# esp8266player3.net
KiCad netlist of a schematic drawn in EAGLE
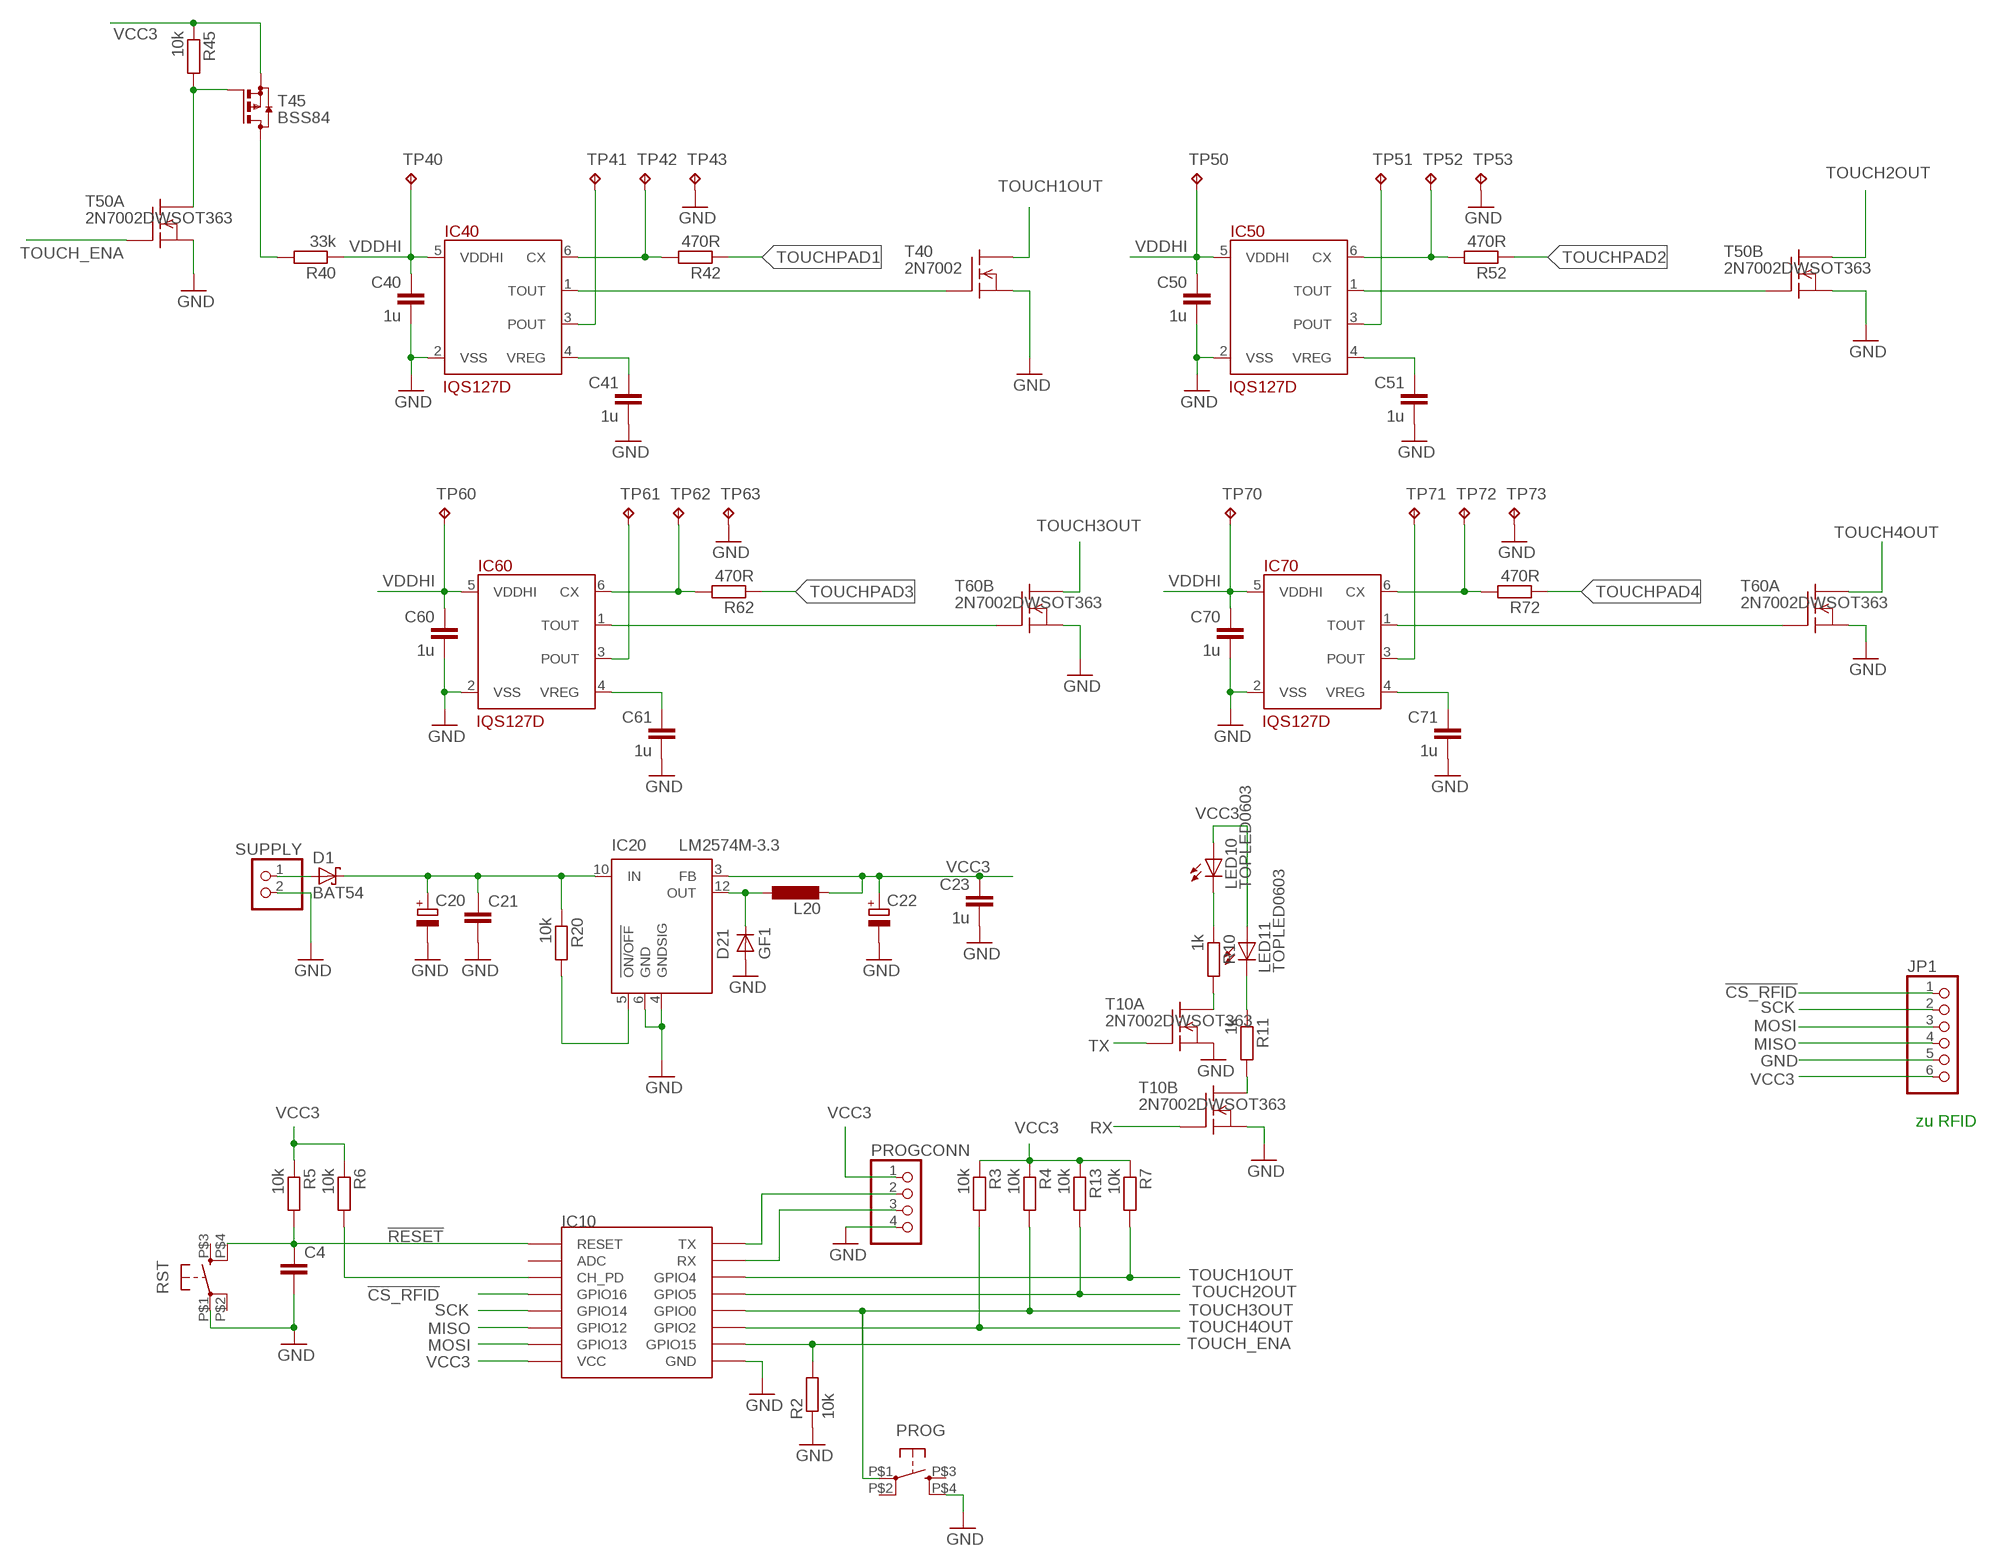
[diagram p0: schematic, sheet 1]

(export (version "E")
  (design (tool "Eeschema 10.0.6"))
  (components
    (comp (ref "C4")
      (value "C-EUC0603")
      (footprint "eagle-import:C0603")
      (libsource (lib "eagle-import") (part "C-EUC0603"))
    )
    (comp (ref "C20")
      (value "CPOL-EUC")
      (footprint "eagle-import:PANASONIC_C")
      (libsource (lib "eagle-import") (part "CPOL-EUC"))
    )
    (comp (ref "C21")
      (value "C-EUC1206")
      (footprint "eagle-import:C1206")
      (libsource (lib "eagle-import") (part "C-EUC1206"))
    )
    (comp (ref "C22")
      (value "CPOL-EUF")
      (footprint "eagle-import:PANASONIC_F")
      (libsource (lib "eagle-import") (part "CPOL-EUF"))
    )
    (comp (ref "C23")
      (value "1u")
      (footprint "eagle-import:C0603")
      (libsource (lib "eagle-import") (part "C-EUC0603"))
    )
    (comp (ref "C40")
      (value "1u")
      (footprint "eagle-import:C0603")
      (libsource (lib "eagle-import") (part "C-EUC0603"))
    )
    (comp (ref "C41")
      (value "1u")
      (footprint "eagle-import:C0603")
      (libsource (lib "eagle-import") (part "C-EUC0603"))
    )
    (comp (ref "C50")
      (value "1u")
      (footprint "eagle-import:C0603")
      (libsource (lib "eagle-import") (part "C-EUC0603"))
    )
    (comp (ref "C51")
      (value "1u")
      (footprint "eagle-import:C0603")
      (libsource (lib "eagle-import") (part "C-EUC0603"))
    )
    (comp (ref "C60")
      (value "1u")
      (footprint "eagle-import:C0603")
      (libsource (lib "eagle-import") (part "C-EUC0603"))
    )
    (comp (ref "C61")
      (value "1u")
      (footprint "eagle-import:C0603")
      (libsource (lib "eagle-import") (part "C-EUC0603"))
    )
    (comp (ref "C70")
      (value "1u")
      (footprint "eagle-import:C0603")
      (libsource (lib "eagle-import") (part "C-EUC0603"))
    )
    (comp (ref "C71")
      (value "1u")
      (footprint "eagle-import:C0603")
      (libsource (lib "eagle-import") (part "C-EUC0603"))
    )
    (comp (ref "D1")
      (value "BAT54")
      (footprint "eagle-import:SOT23")
      (libsource (lib "eagle-import") (part "BAT54"))
    )
    (comp (ref "D21")
      (value "GF1")
      (footprint "eagle-import:SMA-DO214AC")
      (libsource (lib "eagle-import") (part "GF1"))
    )
    (comp (ref "IC10")
      (value "ESP12SMD")
      (footprint "eagle-import:ESP12-SMD")
      (libsource (lib "eagle-import") (part "ESP12SMD"))
    )
    (comp (ref "IC20")
      (value "LM2574M-3.3")
      (footprint "eagle-import:SO14W")
      (libsource (lib "eagle-import") (part "LM2574?-M3.3"))
    )
    (comp (ref "IC40")
      (value "IQS127D")
      (footprint "eagle-import:SOT23-6")
      (libsource (lib "eagle-import") (part "IQS127D"))
    )
    (comp (ref "IC50")
      (value "IQS127D")
      (footprint "eagle-import:SOT23-6")
      (libsource (lib "eagle-import") (part "IQS127D"))
    )
    (comp (ref "IC60")
      (value "IQS127D")
      (footprint "eagle-import:SOT23-6")
      (libsource (lib "eagle-import") (part "IQS127D"))
    )
    (comp (ref "IC70")
      (value "IQS127D")
      (footprint "eagle-import:SOT23-6")
      (libsource (lib "eagle-import") (part "IQS127D"))
    )
    (comp (ref "JP1")
      (value "PINHD-1X6")
      (footprint "eagle-import:1X06")
      (libsource (lib "eagle-import") (part "PINHD-1X6"))
    )
    (comp (ref "L20")
      (value "L-EUSRR0603")
      (footprint "eagle-import:SRR6603-BOURNS")
      (libsource (lib "eagle-import") (part "L-EUSRR0603"))
    )
    (comp (ref "LED10")
      (value "TOPLED0603")
      (footprint "eagle-import:LED-0603-OSRAM")
      (libsource (lib "eagle-import") (part "TOPLED0603"))
    )
    (comp (ref "LED11")
      (value "TOPLED0603")
      (footprint "eagle-import:LED-0603-OSRAM")
      (libsource (lib "eagle-import") (part "TOPLED0603"))
    )
    (comp (ref "PROG")
      (value "10-XXTL3305")
      (footprint "eagle-import:TL3305")
      (libsource (lib "eagle-import") (part "10-XXTL3305"))
    )
    (comp (ref "PROGCONN")
      (value "PINHD-1X4")
      (footprint "eagle-import:1X04")
      (libsource (lib "eagle-import") (part "PINHD-1X4"))
    )
    (comp (ref "R2")
      (value "10k")
      (footprint "eagle-import:R0603@1")
      (libsource (lib "eagle-import") (part "R-EU_R0603"))
    )
    (comp (ref "R3")
      (value "10k")
      (footprint "eagle-import:R0603@1")
      (libsource (lib "eagle-import") (part "R-EU_R0603"))
    )
    (comp (ref "R4")
      (value "10k")
      (footprint "eagle-import:R0603@1")
      (libsource (lib "eagle-import") (part "R-EU_R0603"))
    )
    (comp (ref "R5")
      (value "10k")
      (footprint "eagle-import:R0603@1")
      (libsource (lib "eagle-import") (part "R-EU_R0603"))
    )
    (comp (ref "R6")
      (value "10k")
      (footprint "eagle-import:R0603@1")
      (libsource (lib "eagle-import") (part "R-EU_R0603"))
    )
    (comp (ref "R7")
      (value "10k")
      (footprint "eagle-import:R0603@1")
      (libsource (lib "eagle-import") (part "R-EU_R0603"))
    )
    (comp (ref "R10")
      (value "1k")
      (footprint "eagle-import:R0603@1")
      (libsource (lib "eagle-import") (part "R-EU_R0603"))
    )
    (comp (ref "R11")
      (value "1k")
      (footprint "eagle-import:R0603@1")
      (libsource (lib "eagle-import") (part "R-EU_R0603"))
    )
    (comp (ref "R13")
      (value "10k")
      (footprint "eagle-import:R0603@1")
      (libsource (lib "eagle-import") (part "R-EU_R0603"))
    )
    (comp (ref "R20")
      (value "10k")
      (footprint "eagle-import:R0603@1")
      (libsource (lib "eagle-import") (part "R-EU_R0603"))
    )
    (comp (ref "R40")
      (value "33k")
      (footprint "eagle-import:R0603@1")
      (libsource (lib "eagle-import") (part "R-EU_R0603"))
    )
    (comp (ref "R42")
      (value "470R")
      (footprint "eagle-import:R0603@1")
      (libsource (lib "eagle-import") (part "R-EU_R0603"))
    )
    (comp (ref "R45")
      (value "10k")
      (footprint "eagle-import:R0603@1")
      (libsource (lib "eagle-import") (part "R-EU_R0603"))
    )
    (comp (ref "R52")
      (value "470R")
      (footprint "eagle-import:R0603@1")
      (libsource (lib "eagle-import") (part "R-EU_R0603"))
    )
    (comp (ref "R62")
      (value "470R")
      (footprint "eagle-import:R0603@1")
      (libsource (lib "eagle-import") (part "R-EU_R0603"))
    )
    (comp (ref "R72")
      (value "470R")
      (footprint "eagle-import:R0603@1")
      (libsource (lib "eagle-import") (part "R-EU_R0603"))
    )
    (comp (ref "RST")
      (value "10-XXTL3305")
      (footprint "eagle-import:TL3305")
      (libsource (lib "eagle-import") (part "10-XXTL3305"))
    )
    (comp (ref "SUPPLY")
      (value "PINHD-1X2")
      (footprint "eagle-import:1X02")
      (libsource (lib "eagle-import") (part "PINHD-1X2"))
    )
    (comp (ref "T10")
      (value "2N7002DWSOT363")
      (footprint "eagle-import:SOT363")
      (libsource (lib "eagle-import") (part "2N7002DWSOT363"))
    )
    (comp (ref "T40")
      (value "2N7002")
      (footprint "eagle-import:SOT23")
      (libsource (lib "eagle-import") (part "2N7002"))
    )
    (comp (ref "T45")
      (value "BSS84")
      (footprint "eagle-import:SOT23")
      (libsource (lib "eagle-import") (part "BSS84"))
    )
    (comp (ref "T50")
      (value "2N7002DWSOT363")
      (footprint "eagle-import:SOT363")
      (libsource (lib "eagle-import") (part "2N7002DWSOT363"))
    )
    (comp (ref "T60")
      (value "2N7002DWSOT363")
      (footprint "eagle-import:SOT363")
      (libsource (lib "eagle-import") (part "2N7002DWSOT363"))
    )
    (comp (ref "TP40")
      (value "TPB1,27")
      (footprint "eagle-import:B1,27")
      (libsource (lib "eagle-import") (part "TPB1,27"))
    )
    (comp (ref "TP41")
      (value "TPB1,27")
      (footprint "eagle-import:B1,27")
      (libsource (lib "eagle-import") (part "TPB1,27"))
    )
    (comp (ref "TP42")
      (value "TPB1,27")
      (footprint "eagle-import:B1,27")
      (libsource (lib "eagle-import") (part "TPB1,27"))
    )
    (comp (ref "TP43")
      (value "TPB1,27")
      (footprint "eagle-import:B1,27")
      (libsource (lib "eagle-import") (part "TPB1,27"))
    )
    (comp (ref "TP50")
      (value "TPB1,27")
      (footprint "eagle-import:B1,27")
      (libsource (lib "eagle-import") (part "TPB1,27"))
    )
    (comp (ref "TP51")
      (value "TPB1,27")
      (footprint "eagle-import:B1,27")
      (libsource (lib "eagle-import") (part "TPB1,27"))
    )
    (comp (ref "TP52")
      (value "TPB1,27")
      (footprint "eagle-import:B1,27")
      (libsource (lib "eagle-import") (part "TPB1,27"))
    )
    (comp (ref "TP53")
      (value "TPB1,27")
      (footprint "eagle-import:B1,27")
      (libsource (lib "eagle-import") (part "TPB1,27"))
    )
    (comp (ref "TP60")
      (value "TPB1,27")
      (footprint "eagle-import:B1,27")
      (libsource (lib "eagle-import") (part "TPB1,27"))
    )
    (comp (ref "TP61")
      (value "TPB1,27")
      (footprint "eagle-import:B1,27")
      (libsource (lib "eagle-import") (part "TPB1,27"))
    )
    (comp (ref "TP62")
      (value "TPB1,27")
      (footprint "eagle-import:B1,27")
      (libsource (lib "eagle-import") (part "TPB1,27"))
    )
    (comp (ref "TP63")
      (value "TPB1,27")
      (footprint "eagle-import:B1,27")
      (libsource (lib "eagle-import") (part "TPB1,27"))
    )
    (comp (ref "TP70")
      (value "TPB1,27")
      (footprint "eagle-import:B1,27")
      (libsource (lib "eagle-import") (part "TPB1,27"))
    )
    (comp (ref "TP71")
      (value "TPB1,27")
      (footprint "eagle-import:B1,27")
      (libsource (lib "eagle-import") (part "TPB1,27"))
    )
    (comp (ref "TP72")
      (value "TPB1,27")
      (footprint "eagle-import:B1,27")
      (libsource (lib "eagle-import") (part "TPB1,27"))
    )
    (comp (ref "TP73")
      (value "TPB1,27")
      (footprint "eagle-import:B1,27")
      (libsource (lib "eagle-import") (part "TPB1,27"))
    )
  )
  (nets
    (net (code "1") (name "/MISO") (class "Default")
      (node (ref "IC10") (pin "GPIO12") (pinfunction "GPIO12_GPIO12") (pintype "bidirectional"))
      (node (ref "JP1") (pin "4") (pinfunction "4_4") (pintype "passive"))
    )
    (net (code "2") (name "/MOSI") (class "Default")
      (node (ref "IC10") (pin "GPIO13") (pinfunction "GPIO13_GPIO13") (pintype "bidirectional"))
      (node (ref "JP1") (pin "3") (pinfunction "3_3") (pintype "passive"))
    )
    (net (code "3") (name "/RX") (class "Default")
      (node (ref "IC10") (pin "RXD0") (pinfunction "RX_RXD0") (pintype "bidirectional"))
      (node (ref "PROGCONN") (pin "3") (pinfunction "3_3") (pintype "passive"))
      (node (ref "T10") (pin "2") (pinfunction "G_2") (pintype "passive"))
    )
    (net (code "4") (name "/SCK") (class "Default")
      (node (ref "IC10") (pin "GPIO14") (pinfunction "GPIO14_GPIO14") (pintype "bidirectional"))
      (node (ref "JP1") (pin "2") (pinfunction "2_2") (pintype "passive"))
    )
    (net (code "5") (name "/TOUCH1OUT") (class "Default")
      (node (ref "IC10") (pin "GPIO4") (pinfunction "GPIO4_GPIO4") (pintype "bidirectional"))
      (node (ref "R7") (pin "2") (pinfunction "2_2") (pintype "passive"))
      (node (ref "T40") (pin "3") (pinfunction "D_3") (pintype "passive"))
    )
    (net (code "6") (name "/TOUCH2OUT") (class "Default")
      (node (ref "IC10") (pin "GPIO5") (pinfunction "GPIO5_GPIO5") (pintype "bidirectional"))
      (node (ref "R13") (pin "2") (pinfunction "2_2") (pintype "passive"))
      (node (ref "T50") (pin "6") (pinfunction "D_6") (pintype "passive"))
    )
    (net (code "7") (name "/TOUCH3OUT") (class "Default")
      (node (ref "IC10") (pin "GPIO0") (pinfunction "GPIO0_GPIO0") (pintype "bidirectional"))
      (node (ref "PROG") (pin "P$1") (pinfunction "P_P$1") (pintype "passive"))
      (node (ref "R4") (pin "2") (pinfunction "2_2") (pintype "passive"))
      (node (ref "T60") (pin "6") (pinfunction "D_6") (pintype "passive"))
    )
    (net (code "8") (name "/TOUCH4OUT") (class "Default")
      (node (ref "IC10") (pin "GPIO2") (pinfunction "GPIO2_GPIO2") (pintype "bidirectional"))
      (node (ref "R3") (pin "2") (pinfunction "2_2") (pintype "passive"))
      (node (ref "T60") (pin "3") (pinfunction "D_3") (pintype "passive"))
    )
    (net (code "9") (name "/TOUCH_ENA") (class "Default")
      (node (ref "IC10") (pin "GPIO15") (pinfunction "GPIO15_GPIO15") (pintype "bidirectional"))
      (node (ref "R2") (pin "2") (pinfunction "2_2") (pintype "passive"))
      (node (ref "T50") (pin "5") (pinfunction "G_5") (pintype "passive"))
    )
    (net (code "10") (name "/TX") (class "Default")
      (node (ref "IC10") (pin "TXD0") (pinfunction "TX_TXD0") (pintype "bidirectional"))
      (node (ref "PROGCONN") (pin "2") (pinfunction "2_2") (pintype "passive"))
      (node (ref "T10") (pin "5") (pinfunction "G_5") (pintype "passive"))
    )
    (net (code "11") (name "/VCC3") (class "Default")
      (node (ref "C22") (pin "+") (pinfunction "+_+") (pintype "passive"))
      (node (ref "C23") (pin "1") (pinfunction "1_1") (pintype "passive"))
      (node (ref "IC10") (pin "VCC") (pinfunction "VCC_VCC") (pintype "bidirectional"))
      (node (ref "IC20") (pin "3") (pinfunction "FB_3") (pintype "input"))
      (node (ref "JP1") (pin "6") (pinfunction "6_6") (pintype "passive"))
      (node (ref "L20") (pin "2") (pinfunction "2_2") (pintype "passive"))
      (node (ref "LED10") (pin "A@1") (pinfunction "A_A@1") (pintype "passive"))
      (node (ref "LED11") (pin "A@1") (pinfunction "A_A@1") (pintype "passive"))
      (node (ref "PROGCONN") (pin "1") (pinfunction "1_1") (pintype "passive"))
      (node (ref "R13") (pin "1") (pinfunction "1_1") (pintype "passive"))
      (node (ref "R3") (pin "1") (pinfunction "1_1") (pintype "passive"))
      (node (ref "R4") (pin "1") (pinfunction "1_1") (pintype "passive"))
      (node (ref "R45") (pin "1") (pinfunction "1_1") (pintype "passive"))
      (node (ref "R5") (pin "1") (pinfunction "1_1") (pintype "passive"))
      (node (ref "R6") (pin "1") (pinfunction "1_1") (pintype "passive"))
      (node (ref "R7") (pin "1") (pinfunction "1_1") (pintype "passive"))
      (node (ref "T45") (pin "2") (pinfunction "S_2") (pintype "passive"))
    )
    (net (code "12") (name "/VDDHI") (class "Default")
      (node (ref "C40") (pin "1") (pinfunction "1_1") (pintype "passive"))
      (node (ref "C50") (pin "1") (pinfunction "1_1") (pintype "passive"))
      (node (ref "C60") (pin "1") (pinfunction "1_1") (pintype "passive"))
      (node (ref "C70") (pin "1") (pinfunction "1_1") (pintype "passive"))
      (node (ref "IC40") (pin "5") (pinfunction "VDDHI_5") (pintype "power_in"))
      (node (ref "IC50") (pin "5") (pinfunction "VDDHI_5") (pintype "power_in"))
      (node (ref "IC60") (pin "5") (pinfunction "VDDHI_5") (pintype "power_in"))
      (node (ref "IC70") (pin "5") (pinfunction "VDDHI_5") (pintype "power_in"))
      (node (ref "R40") (pin "1") (pinfunction "1_1") (pintype "passive"))
      (node (ref "TP40") (pin "TP") (pinfunction "TP_TP") (pintype "input"))
      (node (ref "TP50") (pin "TP") (pinfunction "TP_TP") (pintype "input"))
      (node (ref "TP60") (pin "TP") (pinfunction "TP_TP") (pintype "input"))
      (node (ref "TP70") (pin "TP") (pinfunction "TP_TP") (pintype "input"))
    )
    (net (code "13") (name "/~{CS_RFID}") (class "Default")
      (node (ref "IC10") (pin "GPIO16") (pinfunction "GPIO16_GPIO16") (pintype "bidirectional"))
      (node (ref "JP1") (pin "1") (pinfunction "1_1") (pintype "passive"))
    )
    (net (code "14") (name "/~{RESET}") (class "Default")
      (node (ref "C4") (pin "1") (pinfunction "1_1") (pintype "passive"))
      (node (ref "IC10") (pin "RESET") (pinfunction "RESET_RESET") (pintype "bidirectional"))
      (node (ref "R5") (pin "2") (pinfunction "2_2") (pintype "passive"))
      (node (ref "RST") (pin "P$4") (pinfunction "S1_P$4") (pintype "passive"))
    )
    (net (code "15") (name "GND") (class "Default")
      (node (ref "C20") (pin "-") (pinfunction "-_-") (pintype "passive"))
      (node (ref "C21") (pin "2") (pinfunction "2_2") (pintype "passive"))
      (node (ref "C22") (pin "-") (pinfunction "-_-") (pintype "passive"))
      (node (ref "C23") (pin "2") (pinfunction "2_2") (pintype "passive"))
      (node (ref "C4") (pin "2") (pinfunction "2_2") (pintype "passive"))
      (node (ref "C40") (pin "2") (pinfunction "2_2") (pintype "passive"))
      (node (ref "C41") (pin "2") (pinfunction "2_2") (pintype "passive"))
      (node (ref "C50") (pin "2") (pinfunction "2_2") (pintype "passive"))
      (node (ref "C51") (pin "2") (pinfunction "2_2") (pintype "passive"))
      (node (ref "C60") (pin "2") (pinfunction "2_2") (pintype "passive"))
      (node (ref "C61") (pin "2") (pinfunction "2_2") (pintype "passive"))
      (node (ref "C70") (pin "2") (pinfunction "2_2") (pintype "passive"))
      (node (ref "C71") (pin "2") (pinfunction "2_2") (pintype "passive"))
      (node (ref "D21") (pin "A") (pinfunction "A_A") (pintype "passive"))
      (node (ref "IC10") (pin "GND") (pinfunction "GND_GND") (pintype "bidirectional"))
      (node (ref "IC20") (pin "4") (pinfunction "GNDSIG_4") (pintype "input"))
      (node (ref "IC20") (pin "6") (pinfunction "GND_6") (pintype "power_in"))
      (node (ref "IC40") (pin "2") (pinfunction "VSS_2") (pintype "power_in"))
      (node (ref "IC50") (pin "2") (pinfunction "VSS_2") (pintype "power_in"))
      (node (ref "IC60") (pin "2") (pinfunction "VSS_2") (pintype "power_in"))
      (node (ref "IC70") (pin "2") (pinfunction "VSS_2") (pintype "power_in"))
      (node (ref "JP1") (pin "5") (pinfunction "5_5") (pintype "passive"))
      (node (ref "PROG") (pin "P$4") (pinfunction "S1_P$4") (pintype "passive"))
      (node (ref "PROGCONN") (pin "4") (pinfunction "4_4") (pintype "passive"))
      (node (ref "R2") (pin "1") (pinfunction "1_1") (pintype "passive"))
      (node (ref "RST") (pin "P$1") (pinfunction "P_P$1") (pintype "passive"))
      (node (ref "SUPPLY") (pin "2") (pinfunction "2_2") (pintype "passive"))
      (node (ref "T10") (pin "1") (pinfunction "S_1") (pintype "passive"))
      (node (ref "T10") (pin "4") (pinfunction "S_4") (pintype "passive"))
      (node (ref "T40") (pin "2") (pinfunction "S_2") (pintype "passive"))
      (node (ref "T50") (pin "1") (pinfunction "S_1") (pintype "passive"))
      (node (ref "T50") (pin "4") (pinfunction "S_4") (pintype "passive"))
      (node (ref "T60") (pin "1") (pinfunction "S_1") (pintype "passive"))
      (node (ref "T60") (pin "4") (pinfunction "S_4") (pintype "passive"))
      (node (ref "TP43") (pin "TP") (pinfunction "TP_TP") (pintype "input"))
      (node (ref "TP53") (pin "TP") (pinfunction "TP_TP") (pintype "input"))
      (node (ref "TP63") (pin "TP") (pinfunction "TP_TP") (pintype "input"))
      (node (ref "TP73") (pin "TP") (pinfunction "TP_TP") (pintype "input"))
    )
    (net (code "16") (name "Net-(D1-A)") (class "Default")
      (node (ref "D1") (pin "1") (pinfunction "A_1") (pintype "passive"))
      (node (ref "SUPPLY") (pin "1") (pinfunction "1_1") (pintype "passive"))
    )
    (net (code "17") (name "Net-(D1-C)") (class "Default")
      (node (ref "C20") (pin "+") (pinfunction "+_+") (pintype "passive"))
      (node (ref "C21") (pin "1") (pinfunction "1_1") (pintype "passive"))
      (node (ref "D1") (pin "3") (pinfunction "C_3") (pintype "passive"))
      (node (ref "IC20") (pin "10") (pinfunction "IN_10") (pintype "input"))
      (node (ref "R20") (pin "1") (pinfunction "1_1") (pintype "passive"))
    )
    (net (code "18") (name "Net-(D21-C)") (class "Default")
      (node (ref "D21") (pin "K") (pinfunction "C_K") (pintype "passive"))
      (node (ref "IC20") (pin "12") (pinfunction "OUT_12") (pintype "passive"))
      (node (ref "L20") (pin "1") (pinfunction "1_1") (pintype "passive"))
    )
    (net (code "19") (name "Net-(IC10-PadCH_PD)") (class "Default")
      (node (ref "IC10") (pin "CH_PD") (pinfunction "CH_PD_CH_PD") (pintype "bidirectional"))
      (node (ref "R6") (pin "2") (pinfunction "2_2") (pintype "passive"))
    )
    (net (code "20") (name "Net-(IC20-~{ON{slash}OFF})") (class "Default")
      (node (ref "IC20") (pin "5") (pinfunction "~{ON/OFF}_5") (pintype "input"))
      (node (ref "R20") (pin "2") (pinfunction "2_2") (pintype "passive"))
    )
    (net (code "21") (name "Net-(IC40-CX)") (class "Default")
      (node (ref "IC40") (pin "6") (pinfunction "CX_6") (pintype "bidirectional"))
      (node (ref "R42") (pin "2") (pinfunction "2_2") (pintype "passive"))
      (node (ref "TP42") (pin "TP") (pinfunction "TP_TP") (pintype "input"))
    )
    (net (code "22") (name "Net-(IC40-POUT)") (class "Default")
      (node (ref "IC40") (pin "3") (pinfunction "POUT_3") (pintype "output"))
      (node (ref "TP41") (pin "TP") (pinfunction "TP_TP") (pintype "input"))
    )
    (net (code "23") (name "Net-(IC40-TOUT)") (class "Default")
      (node (ref "IC40") (pin "1") (pinfunction "TOUT_1") (pintype "output"))
      (node (ref "T40") (pin "1") (pinfunction "G_1") (pintype "passive"))
    )
    (net (code "24") (name "Net-(IC40-VREG)") (class "Default")
      (node (ref "C41") (pin "1") (pinfunction "1_1") (pintype "passive"))
      (node (ref "IC40") (pin "4") (pinfunction "VREG_4") (pintype "power_in"))
    )
    (net (code "25") (name "Net-(IC50-CX)") (class "Default")
      (node (ref "IC50") (pin "6") (pinfunction "CX_6") (pintype "bidirectional"))
      (node (ref "R52") (pin "2") (pinfunction "2_2") (pintype "passive"))
      (node (ref "TP52") (pin "TP") (pinfunction "TP_TP") (pintype "input"))
    )
    (net (code "26") (name "Net-(IC50-POUT)") (class "Default")
      (node (ref "IC50") (pin "3") (pinfunction "POUT_3") (pintype "output"))
      (node (ref "TP51") (pin "TP") (pinfunction "TP_TP") (pintype "input"))
    )
    (net (code "27") (name "Net-(IC50-TOUT)") (class "Default")
      (node (ref "IC50") (pin "1") (pinfunction "TOUT_1") (pintype "output"))
      (node (ref "T50") (pin "2") (pinfunction "G_2") (pintype "passive"))
    )
    (net (code "28") (name "Net-(IC50-VREG)") (class "Default")
      (node (ref "C51") (pin "1") (pinfunction "1_1") (pintype "passive"))
      (node (ref "IC50") (pin "4") (pinfunction "VREG_4") (pintype "power_in"))
    )
    (net (code "29") (name "Net-(IC60-CX)") (class "Default")
      (node (ref "IC60") (pin "6") (pinfunction "CX_6") (pintype "bidirectional"))
      (node (ref "R62") (pin "2") (pinfunction "2_2") (pintype "passive"))
      (node (ref "TP62") (pin "TP") (pinfunction "TP_TP") (pintype "input"))
    )
    (net (code "30") (name "Net-(IC60-POUT)") (class "Default")
      (node (ref "IC60") (pin "3") (pinfunction "POUT_3") (pintype "output"))
      (node (ref "TP61") (pin "TP") (pinfunction "TP_TP") (pintype "input"))
    )
    (net (code "31") (name "Net-(IC60-TOUT)") (class "Default")
      (node (ref "IC60") (pin "1") (pinfunction "TOUT_1") (pintype "output"))
      (node (ref "T60") (pin "2") (pinfunction "G_2") (pintype "passive"))
    )
    (net (code "32") (name "Net-(IC60-VREG)") (class "Default")
      (node (ref "C61") (pin "1") (pinfunction "1_1") (pintype "passive"))
      (node (ref "IC60") (pin "4") (pinfunction "VREG_4") (pintype "power_in"))
    )
    (net (code "33") (name "Net-(IC70-CX)") (class "Default")
      (node (ref "IC70") (pin "6") (pinfunction "CX_6") (pintype "bidirectional"))
      (node (ref "R72") (pin "2") (pinfunction "2_2") (pintype "passive"))
      (node (ref "TP72") (pin "TP") (pinfunction "TP_TP") (pintype "input"))
    )
    (net (code "34") (name "Net-(IC70-POUT)") (class "Default")
      (node (ref "IC70") (pin "3") (pinfunction "POUT_3") (pintype "output"))
      (node (ref "TP71") (pin "TP") (pinfunction "TP_TP") (pintype "input"))
    )
    (net (code "35") (name "Net-(IC70-TOUT)") (class "Default")
      (node (ref "IC70") (pin "1") (pinfunction "TOUT_1") (pintype "output"))
      (node (ref "T60") (pin "5") (pinfunction "G_5") (pintype "passive"))
    )
    (net (code "36") (name "Net-(IC70-VREG)") (class "Default")
      (node (ref "C71") (pin "1") (pinfunction "1_1") (pintype "passive"))
      (node (ref "IC70") (pin "4") (pinfunction "VREG_4") (pintype "power_in"))
    )
    (net (code "37") (name "Net-(LED10-C)") (class "Default")
      (node (ref "LED10") (pin "K@1") (pinfunction "C_K@1") (pintype "passive"))
      (node (ref "R10") (pin "1") (pinfunction "1_1") (pintype "passive"))
    )
    (net (code "38") (name "Net-(LED11-C)") (class "Default")
      (node (ref "LED11") (pin "K@1") (pinfunction "C_K@1") (pintype "passive"))
      (node (ref "R11") (pin "1") (pinfunction "1_1") (pintype "passive"))
    )
    (net (code "39") (name "Net-(T10A-D)") (class "Default")
      (node (ref "R10") (pin "2") (pinfunction "2_2") (pintype "passive"))
      (node (ref "T10") (pin "3") (pinfunction "D_3") (pintype "passive"))
    )
    (net (code "40") (name "Net-(T10B-D)") (class "Default")
      (node (ref "R11") (pin "2") (pinfunction "2_2") (pintype "passive"))
      (node (ref "T10") (pin "6") (pinfunction "D_6") (pintype "passive"))
    )
    (net (code "41") (name "Net-(T45-D)") (class "Default")
      (node (ref "R40") (pin "2") (pinfunction "2_2") (pintype "passive"))
      (node (ref "T45") (pin "3") (pinfunction "D_3") (pintype "passive"))
    )
    (net (code "42") (name "Net-(T45-G)") (class "Default")
      (node (ref "R45") (pin "2") (pinfunction "2_2") (pintype "passive"))
      (node (ref "T45") (pin "1") (pinfunction "G_1") (pintype "passive"))
      (node (ref "T50") (pin "3") (pinfunction "D_3") (pintype "passive"))
    )
    (net (code "43") (name "TOUCHPAD1") (class "Default")
      (node (ref "R42") (pin "1") (pinfunction "1_1") (pintype "passive"))
    )
    (net (code "44") (name "TOUCHPAD2") (class "Default")
      (node (ref "R52") (pin "1") (pinfunction "1_1") (pintype "passive"))
    )
    (net (code "45") (name "TOUCHPAD3") (class "Default")
      (node (ref "R62") (pin "1") (pinfunction "1_1") (pintype "passive"))
    )
    (net (code "46") (name "TOUCHPAD4") (class "Default")
      (node (ref "R72") (pin "1") (pinfunction "1_1") (pintype "passive"))
    )
    (net (code "47") (name "unconnected-(IC10-PadADC)") (class "Default")
      (node (ref "IC10") (pin "ADC") (pinfunction "ADC_ADC") (pintype "bidirectional"))
    )
    (net (code "48") (name "unconnected-(PROG-P1-PadP$2)") (class "Default")
      (node (ref "PROG") (pin "P$2") (pinfunction "P1_P$2") (pintype "passive"))
    )
    (net (code "49") (name "unconnected-(PROG-S-PadP$3)") (class "Default")
      (node (ref "PROG") (pin "P$3") (pinfunction "S_P$3") (pintype "passive"))
    )
    (net (code "50") (name "unconnected-(RST-P1-PadP$2)") (class "Default")
      (node (ref "RST") (pin "P$2") (pinfunction "P1_P$2") (pintype "passive"))
    )
    (net (code "51") (name "unconnected-(RST-S-PadP$3)") (class "Default")
      (node (ref "RST") (pin "P$3") (pinfunction "S_P$3") (pintype "passive"))
    )
  )
)
